# MCU.net
KiCad netlist of a schematic drawn in Altium Designer
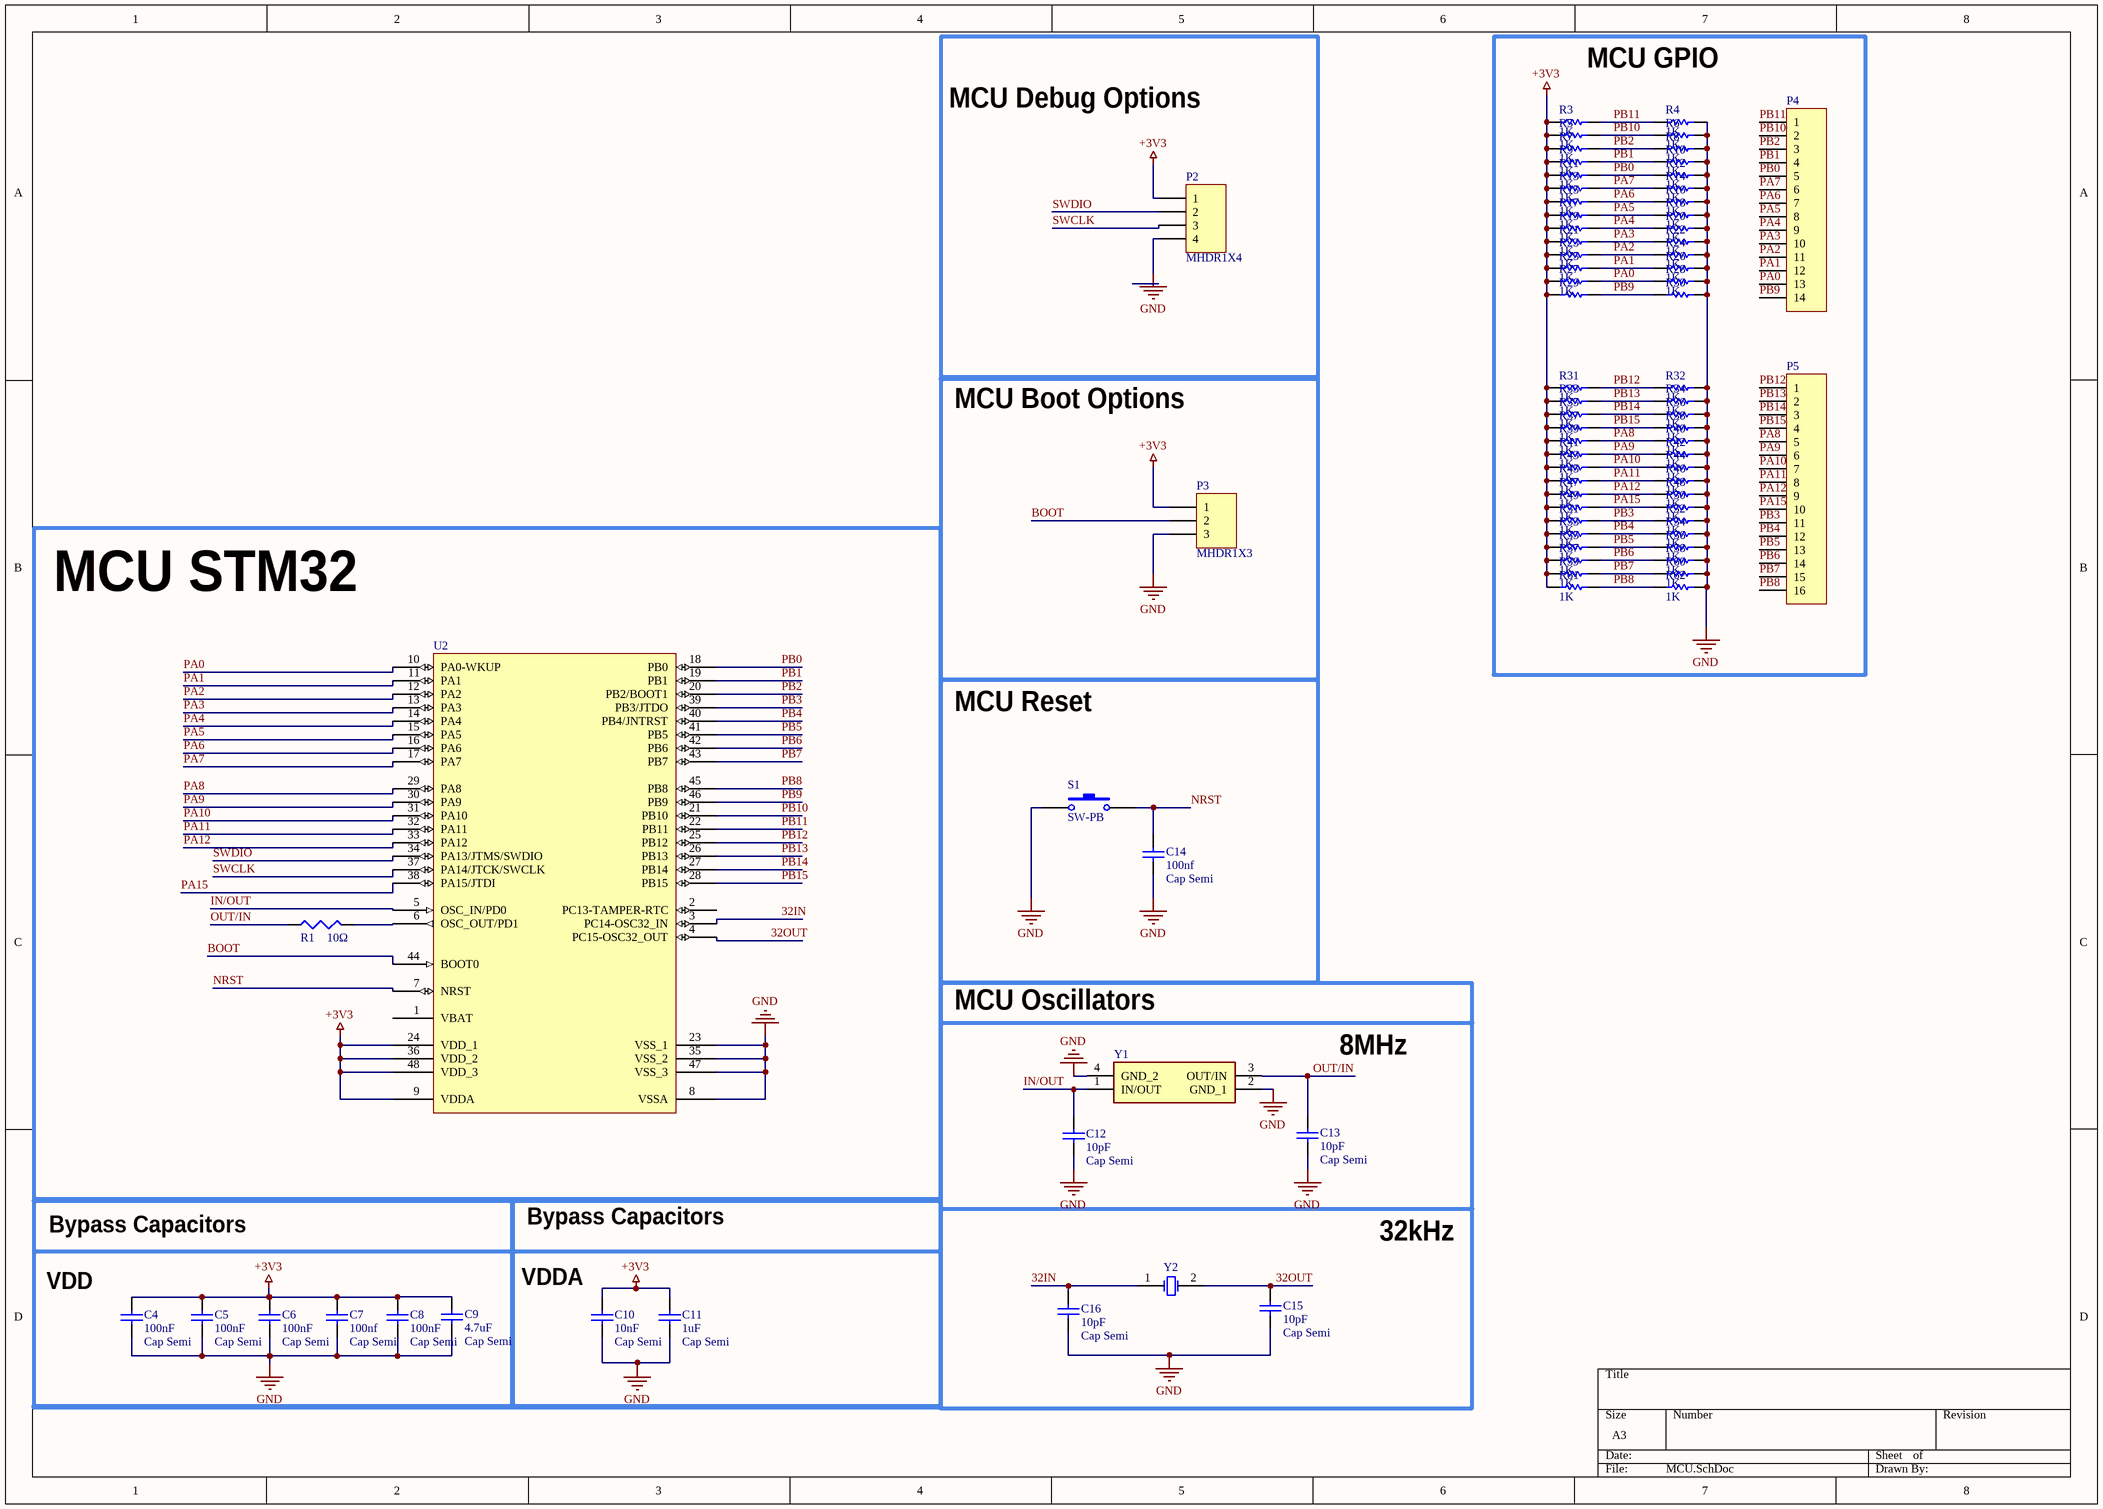
[diagram p0: MCU.SchDoc]

(export (version "E")
  (design (tool "Eeschema 10.0.6"))
  (components
    (comp (ref "C4")
      (value "Cap Semi")
      (footprint "1608[0603]")
      (description "Capacitor (Semiconductor SIM Model)")
      (fields (field (name "ALTIUM_VALUE") "100nF") (field (name "PUBLISHER") "Altium Limited"))
      (libsource (lib "Miscellaneous Devices") (part "Cap Semi"))
    )
    (comp (ref "C5")
      (value "Cap Semi")
      (footprint "1608[0603]")
      (description "Capacitor (Semiconductor SIM Model)")
      (fields (field (name "ALTIUM_VALUE") "100nF") (field (name "PUBLISHER") "Altium Limited"))
      (libsource (lib "Miscellaneous Devices") (part "Cap Semi"))
    )
    (comp (ref "C6")
      (value "Cap Semi")
      (footprint "1608[0603]")
      (description "Capacitor (Semiconductor SIM Model)")
      (fields (field (name "ALTIUM_VALUE") "100nF") (field (name "PUBLISHER") "Altium Limited"))
      (libsource (lib "Miscellaneous Devices") (part "Cap Semi"))
    )
    (comp (ref "C7")
      (value "Cap Semi")
      (footprint "1608[0603]")
      (description "Capacitor (Semiconductor SIM Model)")
      (fields (field (name "ALTIUM_VALUE") "100nf") (field (name "PUBLISHER") "Altium Limited"))
      (libsource (lib "Miscellaneous Devices") (part "Cap Semi"))
    )
    (comp (ref "C8")
      (value "Cap Semi")
      (footprint "1608[0603]")
      (description "Capacitor (Semiconductor SIM Model)")
      (fields (field (name "ALTIUM_VALUE") "100nF") (field (name "PUBLISHER") "Altium Limited"))
      (libsource (lib "Miscellaneous Devices") (part "Cap Semi"))
    )
    (comp (ref "C9")
      (value "Cap Semi")
      (footprint "1608[0603]")
      (description "Capacitor (Semiconductor SIM Model)")
      (fields (field (name "ALTIUM_VALUE") "4.7uF") (field (name "PUBLISHER") "Altium Limited"))
      (libsource (lib "Miscellaneous Devices") (part "Cap Semi"))
    )
    (comp (ref "C10")
      (value "Cap Semi")
      (footprint "1608[0603]")
      (description "Capacitor (Semiconductor SIM Model)")
      (fields (field (name "ALTIUM_VALUE") "10nF") (field (name "PUBLISHER") "Altium Limited"))
      (libsource (lib "Miscellaneous Devices") (part "Cap Semi"))
    )
    (comp (ref "C11")
      (value "Cap Semi")
      (footprint "1608[0603]")
      (description "Capacitor (Semiconductor SIM Model)")
      (fields (field (name "ALTIUM_VALUE") "1uF") (field (name "PUBLISHER") "Altium Limited"))
      (libsource (lib "Miscellaneous Devices") (part "Cap Semi"))
    )
    (comp (ref "C12")
      (value "Cap Semi")
      (footprint "0402")
      (description "Capacitor (Semiconductor SIM Model)")
      (fields (field (name "ALTIUM_VALUE") "10pF") (field (name "PUBLISHER") "Altium Limited"))
      (libsource (lib "Miscellaneous Devices") (part "Cap Semi"))
    )
    (comp (ref "C13")
      (value "Cap Semi")
      (footprint "0402")
      (description "Capacitor (Semiconductor SIM Model)")
      (fields (field (name "ALTIUM_VALUE") "10pF") (field (name "PUBLISHER") "Altium Limited"))
      (libsource (lib "Miscellaneous Devices") (part "Cap Semi"))
    )
    (comp (ref "C14")
      (value "Cap Semi")
      (footprint "1608[0603]")
      (description "Capacitor (Semiconductor SIM Model)")
      (fields (field (name "ALTIUM_VALUE") "100nf") (field (name "PUBLISHER") "Altium Limited"))
      (libsource (lib "Miscellaneous Devices") (part "Cap Semi"))
    )
    (comp (ref "C15")
      (value "Cap Semi")
      (footprint "0402")
      (description "Capacitor (Semiconductor SIM Model)")
      (fields (field (name "ALTIUM_VALUE") "10pF") (field (name "PUBLISHER") "Altium Limited"))
      (libsource (lib "Miscellaneous Devices") (part "Cap Semi"))
    )
    (comp (ref "C16")
      (value "Cap Semi")
      (footprint "0402")
      (description "Capacitor (Semiconductor SIM Model)")
      (fields (field (name "ALTIUM_VALUE") "10pF") (field (name "PUBLISHER") "Altium Limited"))
      (libsource (lib "Miscellaneous Devices") (part "Cap Semi"))
    )
    (comp (ref "P2")
      (value "MHDR1X4")
      (footprint "MHDR1X4")
      (description "Header, 4-Pin")
      (fields (field (name "PUBLISHER") "Altium Limited"))
      (libsource (lib "Miscellaneous Connectors") (part "MHDR1X4"))
    )
    (comp (ref "P3")
      (value "MHDR1X3")
      (footprint "MHDR1X3")
      (description "Header, 3-Pin")
      (fields (field (name "PUBLISHER") "Altium Limited"))
      (libsource (lib "Miscellaneous Connectors") (part "MHDR1X3"))
    )
    (comp (ref "P4")
      (value "Header 14")
      (footprint "My_1X14")
      (description "Header, 14-Pin")
      (fields (field (name "ASID PART NUMBER") "Header 14-AS"))
      (libsource (lib "Mylib+Rev+4") (part "Header 14"))
    )
    (comp (ref "P5")
      (value "Header 16")
      (footprint "MY_FE16")
      (description "Header, 16-Pin")
      (fields (field (name "ASID PART NUMBER") "Header 16-AS"))
      (libsource (lib "Mylib+Rev+4") (part "Header 16"))
    )
    (comp (ref "R1")
      (value "10Ω")
      (footprint "J1-0603")
      (description "Resistor")
      (fields (field (name "Comment") "Res3") (field (name "PUBLISHER") "Altium Limited"))
      (libsource (lib "Miscellaneous Devices") (part "Res3"))
    )
    (comp (ref "R3")
      (value "1K")
      (footprint "MY_0603")
      (description "Standard resistor")
      (fields (field (name "ASID PART NUMBER") "Res-AS"))
      (libsource (lib "Mylib+Rev+4") (part "Res"))
    )
    (comp (ref "R4")
      (value "1K")
      (footprint "MY_0603")
      (description "Standard resistor")
      (fields (field (name "ASID PART NUMBER") "Res-AS"))
      (libsource (lib "Mylib+Rev+4") (part "Res"))
    )
    (comp (ref "R5")
      (value "1K")
      (footprint "MY_0603")
      (description "Standard resistor")
      (fields (field (name "ASID PART NUMBER") "Res-AS"))
      (libsource (lib "Mylib+Rev+4") (part "Res"))
    )
    (comp (ref "R6")
      (value "1K")
      (footprint "MY_0603")
      (description "Standard resistor")
      (fields (field (name "ASID PART NUMBER") "Res-AS"))
      (libsource (lib "Mylib+Rev+4") (part "Res"))
    )
    (comp (ref "R7")
      (value "1K")
      (footprint "MY_0603")
      (description "Standard resistor")
      (fields (field (name "ASID PART NUMBER") "Res-AS"))
      (libsource (lib "Mylib+Rev+4") (part "Res"))
    )
    (comp (ref "R8")
      (value "1K")
      (footprint "MY_0603")
      (description "Standard resistor")
      (fields (field (name "ASID PART NUMBER") "Res-AS"))
      (libsource (lib "Mylib+Rev+4") (part "Res"))
    )
    (comp (ref "R9")
      (value "1K")
      (footprint "MY_0603")
      (description "Standard resistor")
      (fields (field (name "ASID PART NUMBER") "Res-AS"))
      (libsource (lib "Mylib+Rev+4") (part "Res"))
    )
    (comp (ref "R10")
      (value "1K")
      (footprint "MY_0603")
      (description "Standard resistor")
      (fields (field (name "ASID PART NUMBER") "Res-AS"))
      (libsource (lib "Mylib+Rev+4") (part "Res"))
    )
    (comp (ref "R11")
      (value "1K")
      (footprint "MY_0603")
      (description "Standard resistor")
      (fields (field (name "ASID PART NUMBER") "Res-AS"))
      (libsource (lib "Mylib+Rev+4") (part "Res"))
    )
    (comp (ref "R12")
      (value "1K")
      (footprint "MY_0603")
      (description "Standard resistor")
      (fields (field (name "ASID PART NUMBER") "Res-AS"))
      (libsource (lib "Mylib+Rev+4") (part "Res"))
    )
    (comp (ref "R13")
      (value "1K")
      (footprint "MY_0603")
      (description "Standard resistor")
      (fields (field (name "ASID PART NUMBER") "Res-AS"))
      (libsource (lib "Mylib+Rev+4") (part "Res"))
    )
    (comp (ref "R14")
      (value "1K")
      (footprint "MY_0603")
      (description "Standard resistor")
      (fields (field (name "ASID PART NUMBER") "Res-AS"))
      (libsource (lib "Mylib+Rev+4") (part "Res"))
    )
    (comp (ref "R15")
      (value "1K")
      (footprint "MY_0603")
      (description "Standard resistor")
      (fields (field (name "ASID PART NUMBER") "Res-AS"))
      (libsource (lib "Mylib+Rev+4") (part "Res"))
    )
    (comp (ref "R16")
      (value "1K")
      (footprint "MY_0603")
      (description "Standard resistor")
      (fields (field (name "ASID PART NUMBER") "Res-AS"))
      (libsource (lib "Mylib+Rev+4") (part "Res"))
    )
    (comp (ref "R17")
      (value "1K")
      (footprint "MY_0603")
      (description "Standard resistor")
      (fields (field (name "ASID PART NUMBER") "Res-AS"))
      (libsource (lib "Mylib+Rev+4") (part "Res"))
    )
    (comp (ref "R18")
      (value "1K")
      (footprint "MY_0603")
      (description "Standard resistor")
      (fields (field (name "ASID PART NUMBER") "Res-AS"))
      (libsource (lib "Mylib+Rev+4") (part "Res"))
    )
    (comp (ref "R19")
      (value "1K")
      (footprint "MY_0603")
      (description "Standard resistor")
      (fields (field (name "ASID PART NUMBER") "Res-AS"))
      (libsource (lib "Mylib+Rev+4") (part "Res"))
    )
    (comp (ref "R20")
      (value "1K")
      (footprint "MY_0603")
      (description "Standard resistor")
      (fields (field (name "ASID PART NUMBER") "Res-AS"))
      (libsource (lib "Mylib+Rev+4") (part "Res"))
    )
    (comp (ref "R21")
      (value "1K")
      (footprint "MY_0603")
      (description "Standard resistor")
      (fields (field (name "ASID PART NUMBER") "Res-AS"))
      (libsource (lib "Mylib+Rev+4") (part "Res"))
    )
    (comp (ref "R22")
      (value "1K")
      (footprint "MY_0603")
      (description "Standard resistor")
      (fields (field (name "ASID PART NUMBER") "Res-AS"))
      (libsource (lib "Mylib+Rev+4") (part "Res"))
    )
    (comp (ref "R23")
      (value "1K")
      (footprint "MY_0603")
      (description "Standard resistor")
      (fields (field (name "ASID PART NUMBER") "Res-AS"))
      (libsource (lib "Mylib+Rev+4") (part "Res"))
    )
    (comp (ref "R24")
      (value "1K")
      (footprint "MY_0603")
      (description "Standard resistor")
      (fields (field (name "ASID PART NUMBER") "Res-AS"))
      (libsource (lib "Mylib+Rev+4") (part "Res"))
    )
    (comp (ref "R25")
      (value "1K")
      (footprint "MY_0603")
      (description "Standard resistor")
      (fields (field (name "ASID PART NUMBER") "Res-AS"))
      (libsource (lib "Mylib+Rev+4") (part "Res"))
    )
    (comp (ref "R26")
      (value "1K")
      (footprint "MY_0603")
      (description "Standard resistor")
      (fields (field (name "ASID PART NUMBER") "Res-AS"))
      (libsource (lib "Mylib+Rev+4") (part "Res"))
    )
    (comp (ref "R27")
      (value "1K")
      (footprint "MY_0603")
      (description "Standard resistor")
      (fields (field (name "ASID PART NUMBER") "Res-AS"))
      (libsource (lib "Mylib+Rev+4") (part "Res"))
    )
    (comp (ref "R28")
      (value "1K")
      (footprint "MY_0603")
      (description "Standard resistor")
      (fields (field (name "ASID PART NUMBER") "Res-AS"))
      (libsource (lib "Mylib+Rev+4") (part "Res"))
    )
    (comp (ref "R29")
      (value "~")
      (footprint "MY_0603")
      (description "Standard resistor")
      (fields (field (name "ASID PART NUMBER") "Res-AS"))
      (libsource (lib "Mylib+Rev+4") (part "Res"))
    )
    (comp (ref "R30")
      (value "~")
      (footprint "MY_0603")
      (description "Standard resistor")
      (fields (field (name "ASID PART NUMBER") "Res-AS"))
      (libsource (lib "Mylib+Rev+4") (part "Res"))
    )
    (comp (ref "R31")
      (value "1K")
      (footprint "MY_0603")
      (description "Standard resistor")
      (fields (field (name "ASID PART NUMBER") "Res-AS"))
      (libsource (lib "Mylib+Rev+4") (part "Res"))
    )
    (comp (ref "R32")
      (value "1K")
      (footprint "MY_0603")
      (description "Standard resistor")
      (fields (field (name "ASID PART NUMBER") "Res-AS"))
      (libsource (lib "Mylib+Rev+4") (part "Res"))
    )
    (comp (ref "R33")
      (value "1K")
      (footprint "MY_0603")
      (description "Standard resistor")
      (fields (field (name "ASID PART NUMBER") "Res-AS"))
      (libsource (lib "Mylib+Rev+4") (part "Res"))
    )
    (comp (ref "R34")
      (value "1K")
      (footprint "MY_0603")
      (description "Standard resistor")
      (fields (field (name "ASID PART NUMBER") "Res-AS"))
      (libsource (lib "Mylib+Rev+4") (part "Res"))
    )
    (comp (ref "R35")
      (value "1K")
      (footprint "MY_0603")
      (description "Standard resistor")
      (fields (field (name "ASID PART NUMBER") "Res-AS"))
      (libsource (lib "Mylib+Rev+4") (part "Res"))
    )
    (comp (ref "R36")
      (value "1K")
      (footprint "MY_0603")
      (description "Standard resistor")
      (fields (field (name "ASID PART NUMBER") "Res-AS"))
      (libsource (lib "Mylib+Rev+4") (part "Res"))
    )
    (comp (ref "R37")
      (value "1K")
      (footprint "MY_0603")
      (description "Standard resistor")
      (fields (field (name "ASID PART NUMBER") "Res-AS"))
      (libsource (lib "Mylib+Rev+4") (part "Res"))
    )
    (comp (ref "R38")
      (value "1K")
      (footprint "MY_0603")
      (description "Standard resistor")
      (fields (field (name "ASID PART NUMBER") "Res-AS"))
      (libsource (lib "Mylib+Rev+4") (part "Res"))
    )
    (comp (ref "R39")
      (value "1K")
      (footprint "MY_0603")
      (description "Standard resistor")
      (fields (field (name "ASID PART NUMBER") "Res-AS"))
      (libsource (lib "Mylib+Rev+4") (part "Res"))
    )
    (comp (ref "R40")
      (value "1K")
      (footprint "MY_0603")
      (description "Standard resistor")
      (fields (field (name "ASID PART NUMBER") "Res-AS"))
      (libsource (lib "Mylib+Rev+4") (part "Res"))
    )
    (comp (ref "R41")
      (value "1K")
      (footprint "MY_0603")
      (description "Standard resistor")
      (fields (field (name "ASID PART NUMBER") "Res-AS"))
      (libsource (lib "Mylib+Rev+4") (part "Res"))
    )
    (comp (ref "R42")
      (value "1K")
      (footprint "MY_0603")
      (description "Standard resistor")
      (fields (field (name "ASID PART NUMBER") "Res-AS"))
      (libsource (lib "Mylib+Rev+4") (part "Res"))
    )
    (comp (ref "R43")
      (value "1K")
      (footprint "MY_0603")
      (description "Standard resistor")
      (fields (field (name "ASID PART NUMBER") "Res-AS"))
      (libsource (lib "Mylib+Rev+4") (part "Res"))
    )
    (comp (ref "R44")
      (value "1K")
      (footprint "MY_0603")
      (description "Standard resistor")
      (fields (field (name "ASID PART NUMBER") "Res-AS"))
      (libsource (lib "Mylib+Rev+4") (part "Res"))
    )
    (comp (ref "R45")
      (value "1K")
      (footprint "MY_0603")
      (description "Standard resistor")
      (fields (field (name "ASID PART NUMBER") "Res-AS"))
      (libsource (lib "Mylib+Rev+4") (part "Res"))
    )
    (comp (ref "R46")
      (value "1K")
      (footprint "MY_0603")
      (description "Standard resistor")
      (fields (field (name "ASID PART NUMBER") "Res-AS"))
      (libsource (lib "Mylib+Rev+4") (part "Res"))
    )
    (comp (ref "R47")
      (value "1K")
      (footprint "MY_0603")
      (description "Standard resistor")
      (fields (field (name "ASID PART NUMBER") "Res-AS"))
      (libsource (lib "Mylib+Rev+4") (part "Res"))
    )
    (comp (ref "R48")
      (value "1K")
      (footprint "MY_0603")
      (description "Standard resistor")
      (fields (field (name "ASID PART NUMBER") "Res-AS"))
      (libsource (lib "Mylib+Rev+4") (part "Res"))
    )
    (comp (ref "R49")
      (value "1K")
      (footprint "MY_0603")
      (description "Standard resistor")
      (fields (field (name "ASID PART NUMBER") "Res-AS"))
      (libsource (lib "Mylib+Rev+4") (part "Res"))
    )
    (comp (ref "R50")
      (value "1K")
      (footprint "MY_0603")
      (description "Standard resistor")
      (fields (field (name "ASID PART NUMBER") "Res-AS"))
      (libsource (lib "Mylib+Rev+4") (part "Res"))
    )
    (comp (ref "R51")
      (value "1K")
      (footprint "MY_0603")
      (description "Standard resistor")
      (fields (field (name "ASID PART NUMBER") "Res-AS"))
      (libsource (lib "Mylib+Rev+4") (part "Res"))
    )
    (comp (ref "R52")
      (value "1K")
      (footprint "MY_0603")
      (description "Standard resistor")
      (fields (field (name "ASID PART NUMBER") "Res-AS"))
      (libsource (lib "Mylib+Rev+4") (part "Res"))
    )
    (comp (ref "R53")
      (value "1K")
      (footprint "MY_0603")
      (description "Standard resistor")
      (fields (field (name "ASID PART NUMBER") "Res-AS"))
      (libsource (lib "Mylib+Rev+4") (part "Res"))
    )
    (comp (ref "R54")
      (value "1K")
      (footprint "MY_0603")
      (description "Standard resistor")
      (fields (field (name "ASID PART NUMBER") "Res-AS"))
      (libsource (lib "Mylib+Rev+4") (part "Res"))
    )
    (comp (ref "R55")
      (value "1K")
      (footprint "MY_0603")
      (description "Standard resistor")
      (fields (field (name "ASID PART NUMBER") "Res-AS"))
      (libsource (lib "Mylib+Rev+4") (part "Res"))
    )
    (comp (ref "R56")
      (value "1K")
      (footprint "MY_0603")
      (description "Standard resistor")
      (fields (field (name "ASID PART NUMBER") "Res-AS"))
      (libsource (lib "Mylib+Rev+4") (part "Res"))
    )
    (comp (ref "R57")
      (value "1K")
      (footprint "MY_0603")
      (description "Standard resistor")
      (fields (field (name "ASID PART NUMBER") "Res-AS"))
      (libsource (lib "Mylib+Rev+4") (part "Res"))
    )
    (comp (ref "R58")
      (value "1K")
      (footprint "MY_0603")
      (description "Standard resistor")
      (fields (field (name "ASID PART NUMBER") "Res-AS"))
      (libsource (lib "Mylib+Rev+4") (part "Res"))
    )
    (comp (ref "R59")
      (value "1K")
      (footprint "MY_0603")
      (description "Standard resistor")
      (fields (field (name "ASID PART NUMBER") "Res-AS"))
      (libsource (lib "Mylib+Rev+4") (part "Res"))
    )
    (comp (ref "R60")
      (value "1K")
      (footprint "MY_0603")
      (description "Standard resistor")
      (fields (field (name "ASID PART NUMBER") "Res-AS"))
      (libsource (lib "Mylib+Rev+4") (part "Res"))
    )
    (comp (ref "R61")
      (value "1K")
      (footprint "MY_0603")
      (description "Standard resistor")
      (fields (field (name "ASID PART NUMBER") "Res-AS"))
      (libsource (lib "Mylib+Rev+4") (part "Res"))
    )
    (comp (ref "R62")
      (value "1K")
      (footprint "MY_0603")
      (description "Standard resistor")
      (fields (field (name "ASID PART NUMBER") "Res-AS"))
      (libsource (lib "Mylib+Rev+4") (part "Res"))
    )
    (comp (ref "S1")
      (value "SW-PB")
      (footprint "SPST-2")
      (description "Switch")
      (fields (field (name "PUBLISHER") "Altium Limited"))
      (libsource (lib "Miscellaneous Devices") (part "SW-PB"))
    )
    (comp (ref "U2")
      (value "~")
      (footprint "LQFP48_N")
      (description "STM32 ARM-based 32-bit MCU with 64 Kbytes Flash, 48-pin LQFP, Industrial Temperature")
      (fields (field (name "PUBLISHER") "Altium Limited"))
      (libsource (lib "mculib_Real") (part "STM32F103C8T6"))
    )
    (comp (ref "Y1")
      (value "~")
      (footprint "ECS801233JGNTR")
      (description "Crystal or Oscillator")
      (fields
        (field (name "MANUFACTURER_PART_NUMBER") "ECS-80-12-33-JGN-TR")
        (field (name "MOUSER PART NUMBER") "520-80-12-33-JGN-TR")
      )
      (libsource (lib "mculib_Real") (part "ECS-80-12-33-JGN-TR"))
    )
    (comp (ref "Y2")
      (value "~")
      (footprint "R38")
      (description "Crystal Oscillator")
      (fields (field (name "PUBLISHER") "Altium Limited"))
      (libsource (lib "mculib_Real") (part "XTAL"))
    )
  )
  (nets
    (net (code "1") (name "+3V3") (class "Default")
      (node (ref "C10") (pin "2") (pinfunction "2_2") (pintype "passive"))
      (node (ref "C11") (pin "2") (pinfunction "2_2") (pintype "passive"))
      (node (ref "C4") (pin "2") (pinfunction "2_2") (pintype "passive"))
      (node (ref "C5") (pin "2") (pinfunction "2_2") (pintype "passive"))
      (node (ref "C6") (pin "2") (pinfunction "2_2") (pintype "passive"))
      (node (ref "C7") (pin "2") (pinfunction "2_2") (pintype "passive"))
      (node (ref "C8") (pin "2") (pinfunction "2_2") (pintype "passive"))
      (node (ref "C9") (pin "2") (pinfunction "2_2") (pintype "passive"))
      (node (ref "P2") (pin "1") (pinfunction "1_1") (pintype "passive"))
      (node (ref "P3") (pin "1") (pinfunction "1_1") (pintype "passive"))
      (node (ref "R11") (pin "1") (pinfunction "1_1") (pintype "passive"))
      (node (ref "R13") (pin "1") (pinfunction "1_1") (pintype "passive"))
      (node (ref "R15") (pin "1") (pinfunction "1_1") (pintype "passive"))
      (node (ref "R17") (pin "1") (pinfunction "1_1") (pintype "passive"))
      (node (ref "R19") (pin "1") (pinfunction "1_1") (pintype "passive"))
      (node (ref "R21") (pin "1") (pinfunction "1_1") (pintype "passive"))
      (node (ref "R23") (pin "1") (pinfunction "1_1") (pintype "passive"))
      (node (ref "R25") (pin "1") (pinfunction "1_1") (pintype "passive"))
      (node (ref "R27") (pin "1") (pinfunction "1_1") (pintype "passive"))
      (node (ref "R29") (pin "1") (pinfunction "1_1") (pintype "passive"))
      (node (ref "R3") (pin "1") (pinfunction "1_1") (pintype "passive"))
      (node (ref "R31") (pin "1") (pinfunction "1_1") (pintype "passive"))
      (node (ref "R33") (pin "1") (pinfunction "1_1") (pintype "passive"))
      (node (ref "R35") (pin "1") (pinfunction "1_1") (pintype "passive"))
      (node (ref "R37") (pin "1") (pinfunction "1_1") (pintype "passive"))
      (node (ref "R39") (pin "1") (pinfunction "1_1") (pintype "passive"))
      (node (ref "R41") (pin "1") (pinfunction "1_1") (pintype "passive"))
      (node (ref "R43") (pin "1") (pinfunction "1_1") (pintype "passive"))
      (node (ref "R45") (pin "1") (pinfunction "1_1") (pintype "passive"))
      (node (ref "R47") (pin "1") (pinfunction "1_1") (pintype "passive"))
      (node (ref "R49") (pin "1") (pinfunction "1_1") (pintype "passive"))
      (node (ref "R5") (pin "1") (pinfunction "1_1") (pintype "passive"))
      (node (ref "R51") (pin "1") (pinfunction "1_1") (pintype "passive"))
      (node (ref "R53") (pin "1") (pinfunction "1_1") (pintype "passive"))
      (node (ref "R55") (pin "1") (pinfunction "1_1") (pintype "passive"))
      (node (ref "R57") (pin "1") (pinfunction "1_1") (pintype "passive"))
      (node (ref "R59") (pin "1") (pinfunction "1_1") (pintype "passive"))
      (node (ref "R61") (pin "1") (pinfunction "1_1") (pintype "passive"))
      (node (ref "R7") (pin "1") (pinfunction "1_1") (pintype "passive"))
      (node (ref "R9") (pin "1") (pinfunction "1_1") (pintype "passive"))
      (node (ref "U2") (pin "24") (pinfunction "VDD_1_24") (pintype "power_in"))
      (node (ref "U2") (pin "36") (pinfunction "VDD_2_36") (pintype "power_in"))
      (node (ref "U2") (pin "48") (pinfunction "VDD_3_48") (pintype "power_in"))
      (node (ref "U2") (pin "9") (pinfunction "VDDA_9") (pintype "power_in"))
    )
    (net (code "2") (name "/32IN") (class "Default")
      (node (ref "C16") (pin "2") (pinfunction "2_2") (pintype "passive"))
      (node (ref "U2") (pin "3") (pinfunction "PC14-OSC32_IN_3") (pintype "bidirectional"))
      (node (ref "Y2") (pin "1") (pinfunction "OSC1_1") (pintype "passive"))
    )
    (net (code "3") (name "/32OUT") (class "Default")
      (node (ref "C15") (pin "2") (pinfunction "2_2") (pintype "passive"))
      (node (ref "U2") (pin "4") (pinfunction "PC15-OSC32_OUT_4") (pintype "bidirectional"))
      (node (ref "Y2") (pin "2") (pinfunction "OSC2_2") (pintype "passive"))
    )
    (net (code "4") (name "/BOOT") (class "Default")
      (node (ref "P3") (pin "2") (pinfunction "2_2") (pintype "passive"))
      (node (ref "U2") (pin "44") (pinfunction "BOOT0_44") (pintype "input"))
    )
    (net (code "5") (name "/IN{slash}OUT") (class "Default")
      (node (ref "C12") (pin "2") (pinfunction "2_2") (pintype "passive"))
      (node (ref "U2") (pin "5") (pinfunction "OSC_IN/PD0_5") (pintype "input"))
      (node (ref "Y1") (pin "1") (pinfunction "IN/OUT_1") (pintype "passive"))
    )
    (net (code "6") (name "/NRST") (class "Default")
      (node (ref "C14") (pin "2") (pinfunction "2_2") (pintype "passive"))
      (node (ref "S1") (pin "2") (pinfunction "2_2") (pintype "passive"))
      (node (ref "U2") (pin "7") (pinfunction "NRST_7") (pintype "bidirectional"))
    )
    (net (code "7") (name "/OUT{slash}IN") (class "Default")
      (node (ref "C13") (pin "2") (pinfunction "2_2") (pintype "passive"))
      (node (ref "R1") (pin "1") (pinfunction "1_1") (pintype "passive"))
      (node (ref "Y1") (pin "3") (pinfunction "OUT/IN_3") (pintype "passive"))
    )
    (net (code "8") (name "/PA0") (class "Default")
      (node (ref "P4") (pin "13") (pinfunction "13_13") (pintype "passive"))
      (node (ref "R27") (pin "2") (pinfunction "2_2") (pintype "passive"))
      (node (ref "R28") (pin "1") (pinfunction "1_1") (pintype "passive"))
      (node (ref "U2") (pin "10") (pinfunction "PA0-WKUP_10") (pintype "bidirectional"))
    )
    (net (code "9") (name "/PA1") (class "Default")
      (node (ref "P4") (pin "12") (pinfunction "12_12") (pintype "passive"))
      (node (ref "R25") (pin "2") (pinfunction "2_2") (pintype "passive"))
      (node (ref "R26") (pin "1") (pinfunction "1_1") (pintype "passive"))
      (node (ref "U2") (pin "11") (pinfunction "PA1_11") (pintype "bidirectional"))
    )
    (net (code "10") (name "/PA2") (class "Default")
      (node (ref "P4") (pin "11") (pinfunction "11_11") (pintype "passive"))
      (node (ref "R23") (pin "2") (pinfunction "2_2") (pintype "passive"))
      (node (ref "R24") (pin "1") (pinfunction "1_1") (pintype "passive"))
      (node (ref "U2") (pin "12") (pinfunction "PA2_12") (pintype "bidirectional"))
    )
    (net (code "11") (name "/PA3") (class "Default")
      (node (ref "P4") (pin "10") (pinfunction "10_10") (pintype "passive"))
      (node (ref "R21") (pin "2") (pinfunction "2_2") (pintype "passive"))
      (node (ref "R22") (pin "1") (pinfunction "1_1") (pintype "passive"))
      (node (ref "U2") (pin "13") (pinfunction "PA3_13") (pintype "bidirectional"))
    )
    (net (code "12") (name "/PA4") (class "Default")
      (node (ref "P4") (pin "9") (pinfunction "9_9") (pintype "passive"))
      (node (ref "R19") (pin "2") (pinfunction "2_2") (pintype "passive"))
      (node (ref "R20") (pin "1") (pinfunction "1_1") (pintype "passive"))
      (node (ref "U2") (pin "14") (pinfunction "PA4_14") (pintype "bidirectional"))
    )
    (net (code "13") (name "/PA5") (class "Default")
      (node (ref "P4") (pin "8") (pinfunction "8_8") (pintype "passive"))
      (node (ref "R17") (pin "2") (pinfunction "2_2") (pintype "passive"))
      (node (ref "R18") (pin "1") (pinfunction "1_1") (pintype "passive"))
      (node (ref "U2") (pin "15") (pinfunction "PA5_15") (pintype "bidirectional"))
    )
    (net (code "14") (name "/PA6") (class "Default")
      (node (ref "P4") (pin "7") (pinfunction "7_7") (pintype "passive"))
      (node (ref "R15") (pin "2") (pinfunction "2_2") (pintype "passive"))
      (node (ref "R16") (pin "1") (pinfunction "1_1") (pintype "passive"))
      (node (ref "U2") (pin "16") (pinfunction "PA6_16") (pintype "bidirectional"))
    )
    (net (code "15") (name "/PA7") (class "Default")
      (node (ref "P4") (pin "6") (pinfunction "6_6") (pintype "passive"))
      (node (ref "R13") (pin "2") (pinfunction "2_2") (pintype "passive"))
      (node (ref "R14") (pin "1") (pinfunction "1_1") (pintype "passive"))
      (node (ref "U2") (pin "17") (pinfunction "PA7_17") (pintype "bidirectional"))
    )
    (net (code "16") (name "/PA8") (class "Default")
      (node (ref "P5") (pin "5") (pinfunction "5_5") (pintype "passive"))
      (node (ref "R39") (pin "2") (pinfunction "2_2") (pintype "passive"))
      (node (ref "R40") (pin "1") (pinfunction "1_1") (pintype "passive"))
      (node (ref "U2") (pin "29") (pinfunction "PA8_29") (pintype "bidirectional"))
    )
    (net (code "17") (name "/PA9") (class "Default")
      (node (ref "P5") (pin "6") (pinfunction "6_6") (pintype "passive"))
      (node (ref "R41") (pin "2") (pinfunction "2_2") (pintype "passive"))
      (node (ref "R42") (pin "1") (pinfunction "1_1") (pintype "passive"))
      (node (ref "U2") (pin "30") (pinfunction "PA9_30") (pintype "bidirectional"))
    )
    (net (code "18") (name "/PA10") (class "Default")
      (node (ref "P5") (pin "7") (pinfunction "7_7") (pintype "passive"))
      (node (ref "R43") (pin "2") (pinfunction "2_2") (pintype "passive"))
      (node (ref "R44") (pin "1") (pinfunction "1_1") (pintype "passive"))
      (node (ref "U2") (pin "31") (pinfunction "PA10_31") (pintype "bidirectional"))
    )
    (net (code "19") (name "/PA11") (class "Default")
      (node (ref "P5") (pin "8") (pinfunction "8_8") (pintype "passive"))
      (node (ref "R45") (pin "2") (pinfunction "2_2") (pintype "passive"))
      (node (ref "R46") (pin "1") (pinfunction "1_1") (pintype "passive"))
      (node (ref "U2") (pin "32") (pinfunction "PA11_32") (pintype "bidirectional"))
    )
    (net (code "20") (name "/PA12") (class "Default")
      (node (ref "P5") (pin "9") (pinfunction "9_9") (pintype "passive"))
      (node (ref "R47") (pin "2") (pinfunction "2_2") (pintype "passive"))
      (node (ref "R48") (pin "1") (pinfunction "1_1") (pintype "passive"))
      (node (ref "U2") (pin "33") (pinfunction "PA12_33") (pintype "bidirectional"))
    )
    (net (code "21") (name "/PA15") (class "Default")
      (node (ref "P5") (pin "10") (pinfunction "10_10") (pintype "passive"))
      (node (ref "R49") (pin "2") (pinfunction "2_2") (pintype "passive"))
      (node (ref "R50") (pin "1") (pinfunction "1_1") (pintype "passive"))
      (node (ref "U2") (pin "38") (pinfunction "PA15/JTDI_38") (pintype "bidirectional"))
    )
    (net (code "22") (name "/PB0") (class "Default")
      (node (ref "P4") (pin "5") (pinfunction "5_5") (pintype "passive"))
      (node (ref "R11") (pin "2") (pinfunction "2_2") (pintype "passive"))
      (node (ref "R12") (pin "1") (pinfunction "1_1") (pintype "passive"))
      (node (ref "U2") (pin "18") (pinfunction "PB0_18") (pintype "bidirectional"))
    )
    (net (code "23") (name "/PB1") (class "Default")
      (node (ref "P4") (pin "4") (pinfunction "4_4") (pintype "passive"))
      (node (ref "R10") (pin "1") (pinfunction "1_1") (pintype "passive"))
      (node (ref "R9") (pin "2") (pinfunction "2_2") (pintype "passive"))
      (node (ref "U2") (pin "19") (pinfunction "PB1_19") (pintype "bidirectional"))
    )
    (net (code "24") (name "/PB2") (class "Default")
      (node (ref "P4") (pin "3") (pinfunction "3_3") (pintype "passive"))
      (node (ref "R7") (pin "2") (pinfunction "2_2") (pintype "passive"))
      (node (ref "R8") (pin "1") (pinfunction "1_1") (pintype "passive"))
      (node (ref "U2") (pin "20") (pinfunction "PB2/BOOT1_20") (pintype "bidirectional"))
    )
    (net (code "25") (name "/PB3") (class "Default")
      (node (ref "P5") (pin "11") (pinfunction "11_11") (pintype "passive"))
      (node (ref "R51") (pin "2") (pinfunction "2_2") (pintype "passive"))
      (node (ref "R52") (pin "1") (pinfunction "1_1") (pintype "passive"))
      (node (ref "U2") (pin "39") (pinfunction "PB3/JTDO_39") (pintype "bidirectional"))
    )
    (net (code "26") (name "/PB4") (class "Default")
      (node (ref "P5") (pin "12") (pinfunction "12_12") (pintype "passive"))
      (node (ref "R53") (pin "2") (pinfunction "2_2") (pintype "passive"))
      (node (ref "R54") (pin "1") (pinfunction "1_1") (pintype "passive"))
      (node (ref "U2") (pin "40") (pinfunction "PB4/JNTRST_40") (pintype "bidirectional"))
    )
    (net (code "27") (name "/PB5") (class "Default")
      (node (ref "P5") (pin "13") (pinfunction "13_13") (pintype "passive"))
      (node (ref "R55") (pin "2") (pinfunction "2_2") (pintype "passive"))
      (node (ref "R56") (pin "1") (pinfunction "1_1") (pintype "passive"))
      (node (ref "U2") (pin "41") (pinfunction "PB5_41") (pintype "bidirectional"))
    )
    (net (code "28") (name "/PB6") (class "Default")
      (node (ref "P5") (pin "14") (pinfunction "14_14") (pintype "passive"))
      (node (ref "R57") (pin "2") (pinfunction "2_2") (pintype "passive"))
      (node (ref "R58") (pin "1") (pinfunction "1_1") (pintype "passive"))
      (node (ref "U2") (pin "42") (pinfunction "PB6_42") (pintype "bidirectional"))
    )
    (net (code "29") (name "/PB7") (class "Default")
      (node (ref "P5") (pin "15") (pinfunction "15_15") (pintype "passive"))
      (node (ref "R59") (pin "2") (pinfunction "2_2") (pintype "passive"))
      (node (ref "R60") (pin "1") (pinfunction "1_1") (pintype "passive"))
      (node (ref "U2") (pin "43") (pinfunction "PB7_43") (pintype "bidirectional"))
    )
    (net (code "30") (name "/PB8") (class "Default")
      (node (ref "P5") (pin "16") (pinfunction "16_16") (pintype "passive"))
      (node (ref "R61") (pin "2") (pinfunction "2_2") (pintype "passive"))
      (node (ref "R62") (pin "1") (pinfunction "1_1") (pintype "passive"))
      (node (ref "U2") (pin "45") (pinfunction "PB8_45") (pintype "bidirectional"))
    )
    (net (code "31") (name "/PB9") (class "Default")
      (node (ref "P4") (pin "14") (pinfunction "14_14") (pintype "passive"))
      (node (ref "R29") (pin "2") (pinfunction "2_2") (pintype "passive"))
      (node (ref "R30") (pin "1") (pinfunction "1_1") (pintype "passive"))
      (node (ref "U2") (pin "46") (pinfunction "PB9_46") (pintype "bidirectional"))
    )
    (net (code "32") (name "/PB10") (class "Default")
      (node (ref "P4") (pin "2") (pinfunction "2_2") (pintype "passive"))
      (node (ref "R5") (pin "2") (pinfunction "2_2") (pintype "passive"))
      (node (ref "R6") (pin "1") (pinfunction "1_1") (pintype "passive"))
      (node (ref "U2") (pin "21") (pinfunction "PB10_21") (pintype "bidirectional"))
    )
    (net (code "33") (name "/PB11") (class "Default")
      (node (ref "P4") (pin "1") (pinfunction "1_1") (pintype "passive"))
      (node (ref "R3") (pin "2") (pinfunction "2_2") (pintype "passive"))
      (node (ref "R4") (pin "1") (pinfunction "1_1") (pintype "passive"))
      (node (ref "U2") (pin "22") (pinfunction "PB11_22") (pintype "bidirectional"))
    )
    (net (code "34") (name "/PB12") (class "Default")
      (node (ref "P5") (pin "1") (pinfunction "1_1") (pintype "passive"))
      (node (ref "R31") (pin "2") (pinfunction "2_2") (pintype "passive"))
      (node (ref "R32") (pin "1") (pinfunction "1_1") (pintype "passive"))
      (node (ref "U2") (pin "25") (pinfunction "PB12_25") (pintype "bidirectional"))
    )
    (net (code "35") (name "/PB13") (class "Default")
      (node (ref "P5") (pin "2") (pinfunction "2_2") (pintype "passive"))
      (node (ref "R33") (pin "2") (pinfunction "2_2") (pintype "passive"))
      (node (ref "R34") (pin "1") (pinfunction "1_1") (pintype "passive"))
      (node (ref "U2") (pin "26") (pinfunction "PB13_26") (pintype "bidirectional"))
    )
    (net (code "36") (name "/PB14") (class "Default")
      (node (ref "P5") (pin "3") (pinfunction "3_3") (pintype "passive"))
      (node (ref "R35") (pin "2") (pinfunction "2_2") (pintype "passive"))
      (node (ref "R36") (pin "1") (pinfunction "1_1") (pintype "passive"))
      (node (ref "U2") (pin "27") (pinfunction "PB14_27") (pintype "bidirectional"))
    )
    (net (code "37") (name "/PB15") (class "Default")
      (node (ref "P5") (pin "4") (pinfunction "4_4") (pintype "passive"))
      (node (ref "R37") (pin "2") (pinfunction "2_2") (pintype "passive"))
      (node (ref "R38") (pin "1") (pinfunction "1_1") (pintype "passive"))
      (node (ref "U2") (pin "28") (pinfunction "PB15_28") (pintype "bidirectional"))
    )
    (net (code "38") (name "/SWCLK") (class "Default")
      (node (ref "P2") (pin "3") (pinfunction "3_3") (pintype "passive"))
      (node (ref "U2") (pin "37") (pinfunction "PA14/JTCK/SWCLK_37") (pintype "bidirectional"))
    )
    (net (code "39") (name "/SWDIO") (class "Default")
      (node (ref "P2") (pin "2") (pinfunction "2_2") (pintype "passive"))
      (node (ref "U2") (pin "34") (pinfunction "PA13/JTMS/SWDIO_34") (pintype "bidirectional"))
    )
    (net (code "40") (name "GND") (class "Default")
      (node (ref "C10") (pin "1") (pinfunction "1_1") (pintype "passive"))
      (node (ref "C11") (pin "1") (pinfunction "1_1") (pintype "passive"))
      (node (ref "C12") (pin "1") (pinfunction "1_1") (pintype "passive"))
      (node (ref "C13") (pin "1") (pinfunction "1_1") (pintype "passive"))
      (node (ref "C14") (pin "1") (pinfunction "1_1") (pintype "passive"))
      (node (ref "C15") (pin "1") (pinfunction "1_1") (pintype "passive"))
      (node (ref "C16") (pin "1") (pinfunction "1_1") (pintype "passive"))
      (node (ref "C4") (pin "1") (pinfunction "1_1") (pintype "passive"))
      (node (ref "C5") (pin "1") (pinfunction "1_1") (pintype "passive"))
      (node (ref "C6") (pin "1") (pinfunction "1_1") (pintype "passive"))
      (node (ref "C7") (pin "1") (pinfunction "1_1") (pintype "passive"))
      (node (ref "C8") (pin "1") (pinfunction "1_1") (pintype "passive"))
      (node (ref "C9") (pin "1") (pinfunction "1_1") (pintype "passive"))
      (node (ref "P2") (pin "4") (pinfunction "4_4") (pintype "passive"))
      (node (ref "P3") (pin "3") (pinfunction "3_3") (pintype "passive"))
      (node (ref "R10") (pin "2") (pinfunction "2_2") (pintype "passive"))
      (node (ref "R12") (pin "2") (pinfunction "2_2") (pintype "passive"))
      (node (ref "R14") (pin "2") (pinfunction "2_2") (pintype "passive"))
      (node (ref "R16") (pin "2") (pinfunction "2_2") (pintype "passive"))
      (node (ref "R18") (pin "2") (pinfunction "2_2") (pintype "passive"))
      (node (ref "R20") (pin "2") (pinfunction "2_2") (pintype "passive"))
      (node (ref "R22") (pin "2") (pinfunction "2_2") (pintype "passive"))
      (node (ref "R24") (pin "2") (pinfunction "2_2") (pintype "passive"))
      (node (ref "R26") (pin "2") (pinfunction "2_2") (pintype "passive"))
      (node (ref "R28") (pin "2") (pinfunction "2_2") (pintype "passive"))
      (node (ref "R30") (pin "2") (pinfunction "2_2") (pintype "passive"))
      (node (ref "R32") (pin "2") (pinfunction "2_2") (pintype "passive"))
      (node (ref "R34") (pin "2") (pinfunction "2_2") (pintype "passive"))
      (node (ref "R36") (pin "2") (pinfunction "2_2") (pintype "passive"))
      (node (ref "R38") (pin "2") (pinfunction "2_2") (pintype "passive"))
      (node (ref "R4") (pin "2") (pinfunction "2_2") (pintype "passive"))
      (node (ref "R40") (pin "2") (pinfunction "2_2") (pintype "passive"))
      (node (ref "R42") (pin "2") (pinfunction "2_2") (pintype "passive"))
      (node (ref "R44") (pin "2") (pinfunction "2_2") (pintype "passive"))
      (node (ref "R46") (pin "2") (pinfunction "2_2") (pintype "passive"))
      (node (ref "R48") (pin "2") (pinfunction "2_2") (pintype "passive"))
      (node (ref "R50") (pin "2") (pinfunction "2_2") (pintype "passive"))
      (node (ref "R52") (pin "2") (pinfunction "2_2") (pintype "passive"))
      (node (ref "R54") (pin "2") (pinfunction "2_2") (pintype "passive"))
      (node (ref "R56") (pin "2") (pinfunction "2_2") (pintype "passive"))
      (node (ref "R58") (pin "2") (pinfunction "2_2") (pintype "passive"))
      (node (ref "R6") (pin "2") (pinfunction "2_2") (pintype "passive"))
      (node (ref "R60") (pin "2") (pinfunction "2_2") (pintype "passive"))
      (node (ref "R62") (pin "2") (pinfunction "2_2") (pintype "passive"))
      (node (ref "R8") (pin "2") (pinfunction "2_2") (pintype "passive"))
      (node (ref "S1") (pin "1") (pinfunction "1_1") (pintype "passive"))
      (node (ref "U2") (pin "23") (pinfunction "VSS_1_23") (pintype "power_in"))
      (node (ref "U2") (pin "35") (pinfunction "VSS_2_35") (pintype "power_in"))
      (node (ref "U2") (pin "47") (pinfunction "VSS_3_47") (pintype "power_in"))
      (node (ref "U2") (pin "8") (pinfunction "VSSA_8") (pintype "power_in"))
      (node (ref "Y1") (pin "2") (pinfunction "GND_1_2") (pintype "passive"))
      (node (ref "Y1") (pin "4") (pinfunction "GND_2_4") (pintype "passive"))
    )
    (net (code "41") (name "Net-(U2-OSC_OUT{slash}PD1)") (class "Default")
      (node (ref "R1") (pin "2") (pinfunction "2_2") (pintype "passive"))
      (node (ref "U2") (pin "6") (pinfunction "OSC_OUT/PD1_6") (pintype "output"))
    )
    (net (code "42") (name "unconnected-(U2-PC13-TAMPER-RTC-Pad2)") (class "Default")
      (node (ref "U2") (pin "2") (pinfunction "PC13-TAMPER-RTC_2") (pintype "bidirectional"))
    )
    (net (code "43") (name "unconnected-(U2-VBAT-Pad1)") (class "Default")
      (node (ref "U2") (pin "1") (pinfunction "VBAT_1") (pintype "power_in"))
    )
  )
)
